# SCH_NAVVIBE_2026-03-12.net
KiCad netlist of a schematic drawn in EasyEDA
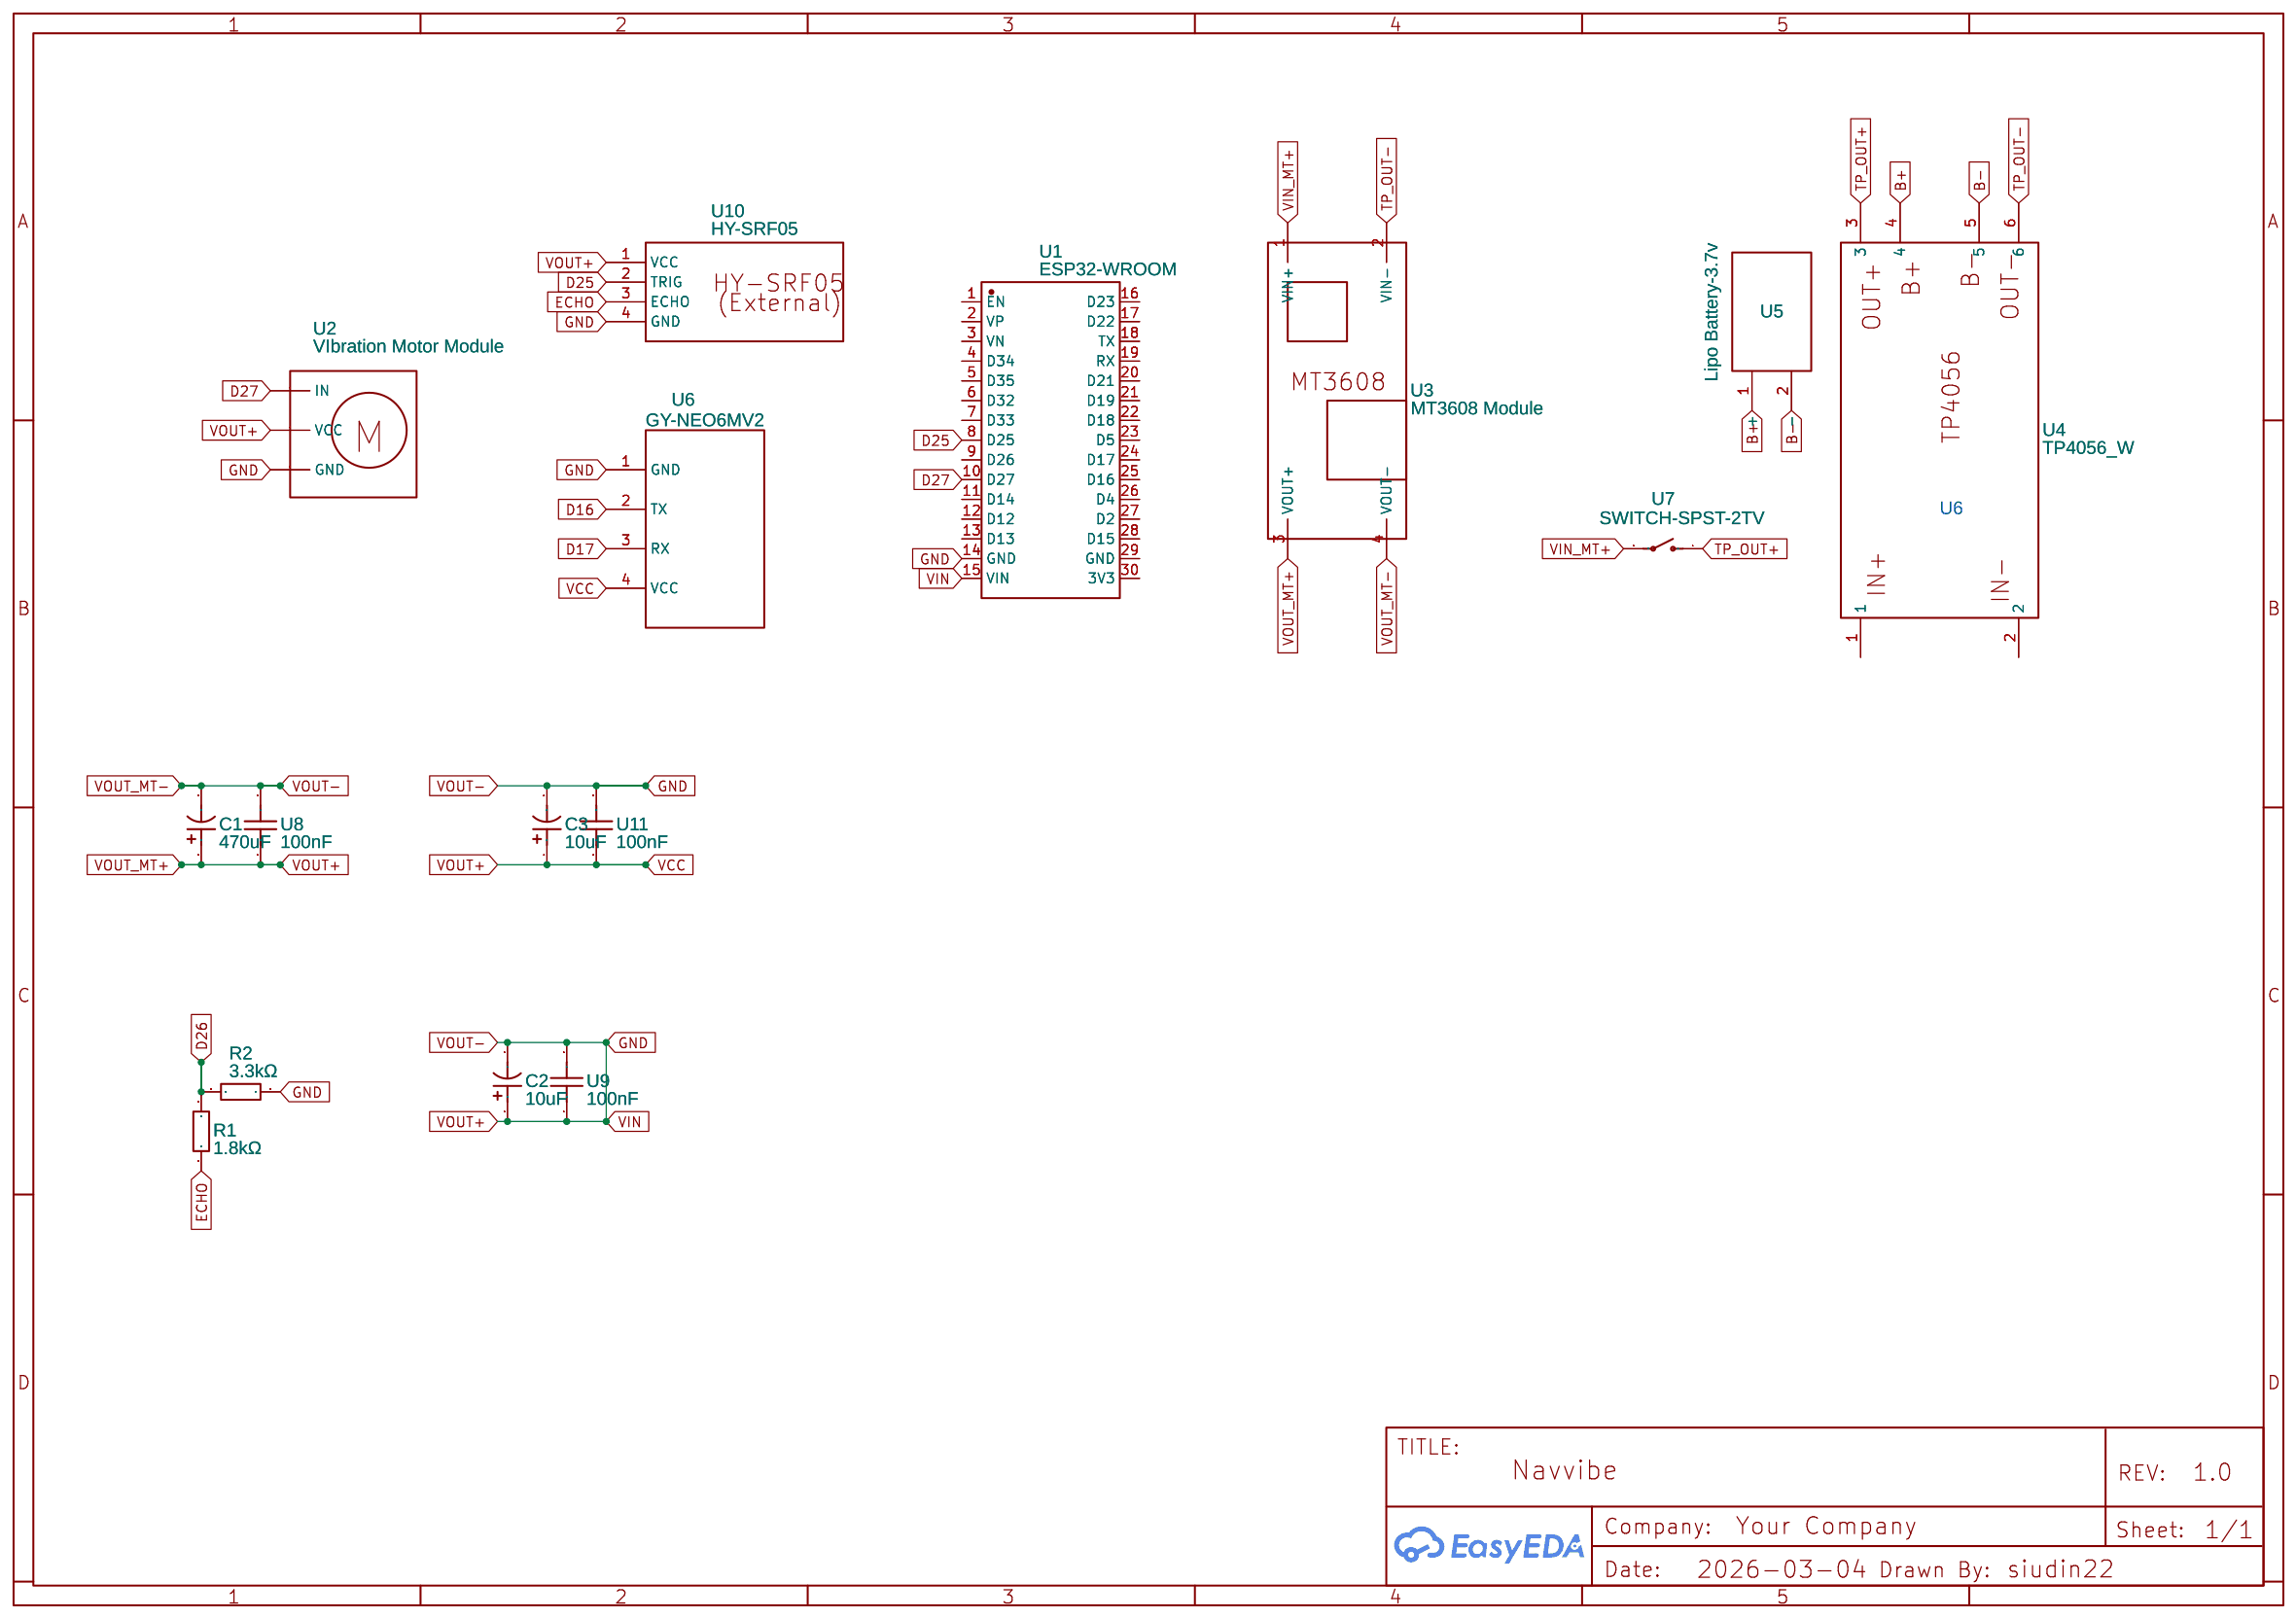
[diagram p0: schematic sheet]

(export (version "E")
  (design (tool "Eeschema 10.0.6"))
  (components
    (comp (ref "C1")
      (value "470uF")
      (fields (field (name "Manufacturer Part") "10V470uF CD288") (field (name "Manufacturer") "HRK(鸿瑞凯电子)"))
      (libsource (lib "") (part "10V470UF CD288"))
    )
    (comp (ref "C2")
      (value "10uF")
      (fields (field (name "Manufacturer Part") "RYHG35V10UF5*8") (field (name "Manufacturer") "HONOR(荣誉)"))
      (libsource (lib "") (part "RYHG35V10UF5*8"))
    )
    (comp (ref "C3")
      (value "10uF")
      (fields (field (name "Manufacturer Part") "RYHG35V10UF5*8") (field (name "Manufacturer") "HONOR(荣誉)"))
      (libsource (lib "") (part "RYHG35V10UF5*8"))
    )
    (comp (ref "R1")
      (value "1.8kΩ")
      (fields
        (field (name "Manufacturer Part") "RN1/2W1.8KΩFT/BA1")
        (field (name "Manufacturer") "Tyohm(幸亚电阻)")
      )
      (libsource (lib "") (part "RN1/2W1.8KΩFT/BA1_1"))
    )
    (comp (ref "R2")
      (value "3.3kΩ")
      (fields
        (field (name "Manufacturer Part") "RN1/2W1.8KΩFT/BA1")
        (field (name "Manufacturer") "Tyohm(幸亚电阻)")
      )
      (libsource (lib "") (part "RN1/2W1.8KΩFT/BA1"))
    )
    (comp (ref "U1")
      (value "ESP32-WROOM")
      (fields
        (field (name "Manufacturer Part") "ESP32 WROOM-32 ESP32-S")
        (field (name "Manufacturer") "ESPRESSIF(乐鑫)")
      )
      (libsource (lib "") (part "ESP32-WROOM"))
    )
    (comp (ref "U2") (value "VIbration Motor Module") (libsource (lib "") (part "VIbration Motor Module")))
    (comp (ref "U3") (value "MT3608 Module") (libsource (lib "") (part "MT3608 Module")))
    (comp (ref "U4") (value "TP4056_W") (libsource (lib "") (part "TP4056_W")))
    (comp (ref "U5") (value "Lipo Battery-3.7v") (libsource (lib "") (part "Lipo Battery-3.7v")))
    (comp (ref "U6") (value "GY-NEO6MV2") (libsource (lib "") (part "GY-NEO6MV2")))
    (comp (ref "U7") (value "SWITCH-SPST-2TV") (libsource (lib "") (part "SWITCH-SPST-2TV")))
    (comp (ref "U8")
      (value "100nF")
      (fields (field (name "Manufacturer Part") "X2 104K310V") (field (name "Manufacturer") "JURCC(捷威电子)"))
      (libsource (lib "") (part "X2 104K310V_C2943725"))
    )
    (comp (ref "U9")
      (value "100nF")
      (fields (field (name "Manufacturer Part") "X2 104K310V") (field (name "Manufacturer") "JURCC(捷威电子)"))
      (libsource (lib "") (part "X2 104K310V_C2943725"))
    )
    (comp (ref "U10") (value "HY-SRF05") (libsource (lib "") (part "HY-SRF05")))
    (comp (ref "U11")
      (value "100nF")
      (fields (field (name "Manufacturer Part") "X2 104K310V") (field (name "Manufacturer") "JURCC(捷威电子)"))
      (libsource (lib "") (part "X2 104K310V_C2943725"))
    )
  )
  (nets
    (net (code "1") (name "B+") (class "Default")
      (node (ref "U4") (pin "4") (pinfunction "4_4") (pintype "unspecified"))
    )
    (net (code "2") (name "B-") (class "Default")
      (node (ref "U4") (pin "5") (pinfunction "5_5") (pintype "unspecified"))
    )
    (net (code "3") (name "D16") (class "Default")
      (node (ref "U6") (pin "2") (pinfunction "TX_2") (pintype "unspecified"))
    )
    (net (code "4") (name "D17") (class "Default")
      (node (ref "U6") (pin "3") (pinfunction "RX_3") (pintype "unspecified"))
    )
    (net (code "5") (name "D25") (class "Default")
      (node (ref "U1") (pin "8") (pinfunction "D25_8") (pintype "unspecified"))
      (node (ref "U10") (pin "2") (pinfunction "TRIG_2") (pintype "input"))
    )
    (net (code "6") (name "D26") (class "Default")
      (node (ref "R1") (pin "2") (pinfunction "2_2") (pintype "unspecified"))
      (node (ref "R2") (pin "2") (pinfunction "2_2") (pintype "unspecified"))
    )
    (net (code "7") (name "D27") (class "Default")
      (node (ref "U1") (pin "10") (pinfunction "D27_10") (pintype "unspecified"))
      (node (ref "U2") (pin "1") (pinfunction "IN_1") (pintype "unspecified"))
    )
    (net (code "8") (name "ECHO") (class "Default")
      (node (ref "R1") (pin "1") (pinfunction "1_1") (pintype "unspecified"))
      (node (ref "U10") (pin "3") (pinfunction "ECHO_3") (pintype "output"))
    )
    (net (code "9") (name "GND") (class "Default")
      (node (ref "C1") (pin "1") (pinfunction "1_1") (pintype "input"))
      (node (ref "C1") (pin "2") (pinfunction "2_2") (pintype "input"))
      (node (ref "C2") (pin "1") (pinfunction "1_1") (pintype "input"))
      (node (ref "C2") (pin "2") (pinfunction "2_2") (pintype "input"))
      (node (ref "C3") (pin "1") (pinfunction "1_1") (pintype "input"))
      (node (ref "C3") (pin "2") (pinfunction "2_2") (pintype "input"))
      (node (ref "R2") (pin "1") (pinfunction "1_1") (pintype "unspecified"))
      (node (ref "U1") (pin "14") (pinfunction "GND_14") (pintype "unspecified"))
      (node (ref "U1") (pin "15") (pinfunction "VIN_15") (pintype "unspecified"))
      (node (ref "U10") (pin "1") (pinfunction "VCC_1") (pintype "passive"))
      (node (ref "U10") (pin "4") (pinfunction "GND_4") (pintype "passive"))
      (node (ref "U11") (pin "1") (pinfunction "1_1") (pintype "unspecified"))
      (node (ref "U11") (pin "2") (pinfunction "2_2") (pintype "unspecified"))
      (node (ref "U2") (pin "2") (pinfunction "VCC_2") (pintype "unspecified"))
      (node (ref "U2") (pin "3") (pinfunction "GND_3") (pintype "unspecified"))
      (node (ref "U3") (pin "3") (pinfunction "VOUT+_3") (pintype "unspecified"))
      (node (ref "U3") (pin "4") (pinfunction "VOUT-_4") (pintype "unspecified"))
      (node (ref "U6") (pin "1") (pinfunction "GND_1") (pintype "unspecified"))
      (node (ref "U6") (pin "4") (pinfunction "VCC_4") (pintype "unspecified"))
      (node (ref "U8") (pin "1") (pinfunction "1_1") (pintype "unspecified"))
      (node (ref "U8") (pin "2") (pinfunction "2_2") (pintype "unspecified"))
      (node (ref "U9") (pin "1") (pinfunction "1_1") (pintype "unspecified"))
      (node (ref "U9") (pin "2") (pinfunction "2_2") (pintype "unspecified"))
    )
    (net (code "10") (name "TP_OUT+") (class "Default")
      (node (ref "U4") (pin "3") (pinfunction "3_3") (pintype "unspecified"))
      (node (ref "U7") (pin "1") (pinfunction "O_1") (pintype "unspecified"))
    )
    (net (code "11") (name "TP_OUT-") (class "Default")
      (node (ref "U3") (pin "2") (pinfunction "VIN-_2") (pintype "unspecified"))
      (node (ref "U4") (pin "6") (pinfunction "6_6") (pintype "unspecified"))
    )
    (net (code "12") (name "VIN_MT+") (class "Default")
      (node (ref "U3") (pin "1") (pinfunction "VIN+_1") (pintype "unspecified"))
      (node (ref "U7") (pin "2") (pinfunction "P_2") (pintype "unspecified"))
    )
    (net (code "13") (name "unconnected-(U1-3V3-Pad30)") (class "Default")
      (node (ref "U1") (pin "30") (pinfunction "3V3_30") (pintype "unspecified"))
    )
    (net (code "14") (name "unconnected-(U1-D2-Pad27)") (class "Default")
      (node (ref "U1") (pin "27") (pinfunction "D2_27") (pintype "unspecified"))
    )
    (net (code "15") (name "unconnected-(U1-D4-Pad26)") (class "Default")
      (node (ref "U1") (pin "26") (pinfunction "D4_26") (pintype "unspecified"))
    )
    (net (code "16") (name "unconnected-(U1-D5-Pad23)") (class "Default")
      (node (ref "U1") (pin "23") (pinfunction "D5_23") (pintype "unspecified"))
    )
    (net (code "17") (name "unconnected-(U1-D12-Pad12)") (class "Default")
      (node (ref "U1") (pin "12") (pinfunction "D12_12") (pintype "unspecified"))
    )
    (net (code "18") (name "unconnected-(U1-D13-Pad13)") (class "Default")
      (node (ref "U1") (pin "13") (pinfunction "D13_13") (pintype "unspecified"))
    )
    (net (code "19") (name "unconnected-(U1-D14-Pad11)") (class "Default")
      (node (ref "U1") (pin "11") (pinfunction "D14_11") (pintype "unspecified"))
    )
    (net (code "20") (name "unconnected-(U1-D15-Pad28)") (class "Default")
      (node (ref "U1") (pin "28") (pinfunction "D15_28") (pintype "unspecified"))
    )
    (net (code "21") (name "unconnected-(U1-D16-Pad25)") (class "Default")
      (node (ref "U1") (pin "25") (pinfunction "D16_25") (pintype "unspecified"))
    )
    (net (code "22") (name "unconnected-(U1-D17-Pad24)") (class "Default")
      (node (ref "U1") (pin "24") (pinfunction "D17_24") (pintype "unspecified"))
    )
    (net (code "23") (name "unconnected-(U1-D18-Pad22)") (class "Default")
      (node (ref "U1") (pin "22") (pinfunction "D18_22") (pintype "unspecified"))
    )
    (net (code "24") (name "unconnected-(U1-D19-Pad21)") (class "Default")
      (node (ref "U1") (pin "21") (pinfunction "D19_21") (pintype "unspecified"))
    )
    (net (code "25") (name "unconnected-(U1-D21-Pad20)") (class "Default")
      (node (ref "U1") (pin "20") (pinfunction "D21_20") (pintype "unspecified"))
    )
    (net (code "26") (name "unconnected-(U1-D22-Pad17)") (class "Default")
      (node (ref "U1") (pin "17") (pinfunction "D22_17") (pintype "unspecified"))
    )
    (net (code "27") (name "unconnected-(U1-D23-Pad16)") (class "Default")
      (node (ref "U1") (pin "16") (pinfunction "D23_16") (pintype "unspecified"))
    )
    (net (code "28") (name "unconnected-(U1-D26-Pad9)") (class "Default")
      (node (ref "U1") (pin "9") (pinfunction "D26_9") (pintype "unspecified"))
    )
    (net (code "29") (name "unconnected-(U1-D32-Pad6)") (class "Default")
      (node (ref "U1") (pin "6") (pinfunction "D32_6") (pintype "unspecified"))
    )
    (net (code "30") (name "unconnected-(U1-D33-Pad7)") (class "Default")
      (node (ref "U1") (pin "7") (pinfunction "D33_7") (pintype "unspecified"))
    )
    (net (code "31") (name "unconnected-(U1-D34-Pad4)") (class "Default")
      (node (ref "U1") (pin "4") (pinfunction "D34_4") (pintype "unspecified"))
    )
    (net (code "32") (name "unconnected-(U1-D35-Pad5)") (class "Default")
      (node (ref "U1") (pin "5") (pinfunction "D35_5") (pintype "unspecified"))
    )
    (net (code "33") (name "unconnected-(U1-EN-Pad1)") (class "Default")
      (node (ref "U1") (pin "1") (pinfunction "EN_1") (pintype "unspecified"))
    )
    (net (code "34") (name "unconnected-(U1-GND-Pad29)") (class "Default")
      (node (ref "U1") (pin "29") (pinfunction "GND_29") (pintype "unspecified"))
    )
    (net (code "35") (name "unconnected-(U1-RX-Pad19)") (class "Default")
      (node (ref "U1") (pin "19") (pinfunction "RX_19") (pintype "unspecified"))
    )
    (net (code "36") (name "unconnected-(U1-TX-Pad18)") (class "Default")
      (node (ref "U1") (pin "18") (pinfunction "TX_18") (pintype "unspecified"))
    )
    (net (code "37") (name "unconnected-(U1-VN-Pad3)") (class "Default")
      (node (ref "U1") (pin "3") (pinfunction "VN_3") (pintype "unspecified"))
    )
    (net (code "38") (name "unconnected-(U1-VP-Pad2)") (class "Default")
      (node (ref "U1") (pin "2") (pinfunction "VP_2") (pintype "unspecified"))
    )
    (net (code "39") (name "unconnected-(U4-Pad1)") (class "Default")
      (node (ref "U4") (pin "1") (pinfunction "1_1") (pintype "unspecified"))
    )
    (net (code "40") (name "unconnected-(U4-Pad2)") (class "Default")
      (node (ref "U4") (pin "2") (pinfunction "2_2") (pintype "unspecified"))
    )
    (net (code "41") (name "unconnected-(U5-+-Pad1)") (class "Default")
      (node (ref "U5") (pin "1") (pinfunction "+_1") (pintype "unspecified"))
    )
    (net (code "42") (name "unconnected-(U5---Pad2)") (class "Default")
      (node (ref "U5") (pin "2") (pinfunction "-_2") (pintype "unspecified"))
    )
  )
)
